# NFCard.net
KiCad netlist of a schematic drawn in Altium Designer
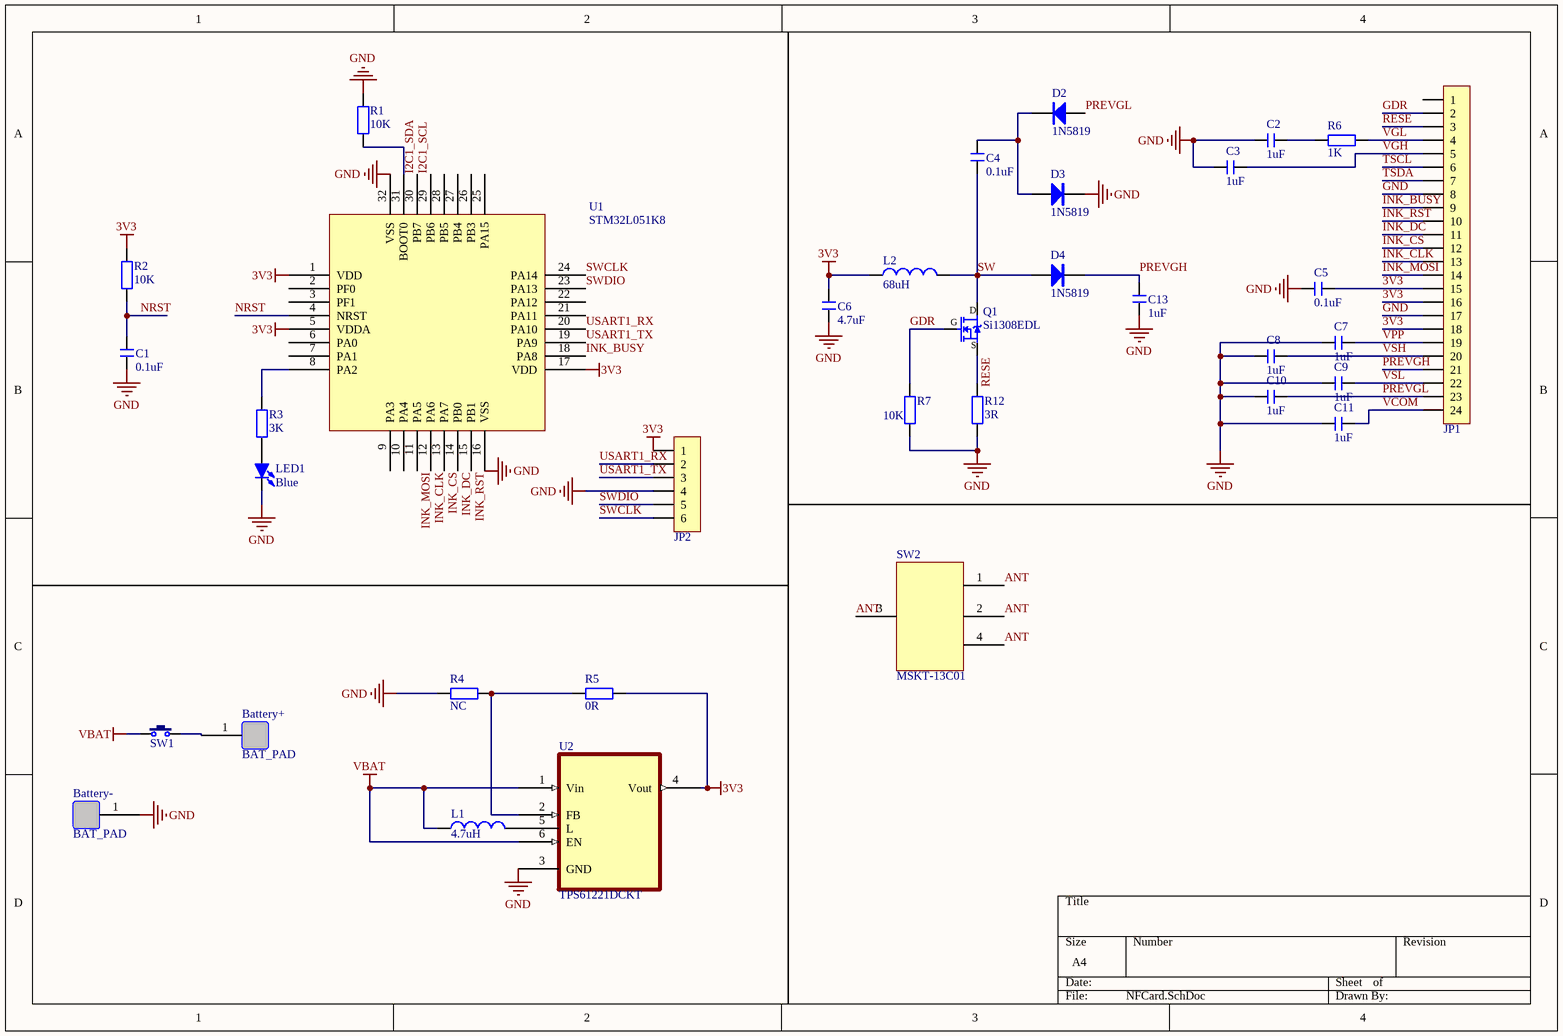
[diagram p0: NFCard.SchDoc]

(export (version "E")
  (design (tool "Eeschema 10.0.6"))
  (components
    (comp (ref "Battery+")
      (value "BAT_PAD")
      (footprint "BAT_PAD")
      (libsource (lib "15.1 - 未分类器件") (part "BAT_PAD"))
    )
    (comp (ref "Battery-")
      (value "BAT_PAD")
      (footprint "BAT_PAD")
      (libsource (lib "15.1 - 未分类器件") (part "BAT_PAD"))
    )
    (comp (ref "C1")
      (value "0.1uF")
      (footprint "C 0603_L")
      (description "无极性贴片电容")
      (fields (field (name "版权归属") "源创客"))
      (libsource (lib "3.1   - 电阻-电容-电感") (part "C"))
    )
    (comp (ref "C2")
      (value "1uF")
      (footprint "C 0603_L")
      (description "无极性贴片电容")
      (fields (field (name "版权归属") "源创客"))
      (libsource (lib "3.1   - 电阻-电容-电感") (part "C"))
    )
    (comp (ref "C3")
      (value "1uF")
      (footprint "C 0603_L")
      (description "无极性贴片电容")
      (fields (field (name "版权归属") "源创客"))
      (libsource (lib "3.1   - 电阻-电容-电感") (part "C"))
    )
    (comp (ref "C4")
      (value "0.1uF")
      (footprint "C 0603_L")
      (description "无极性贴片电容")
      (fields (field (name "版权归属") "源创客"))
      (libsource (lib "3.1   - 电阻-电容-电感") (part "C"))
    )
    (comp (ref "C5")
      (value "0.1uF")
      (footprint "C 0603_L")
      (description "无极性贴片电容")
      (fields (field (name "版权归属") "源创客"))
      (libsource (lib "3.1   - 电阻-电容-电感") (part "C"))
    )
    (comp (ref "C6")
      (value "4.7uF")
      (footprint "C 0603_L")
      (description "无极性贴片电容")
      (fields (field (name "版权归属") "源创客"))
      (libsource (lib "3.1   - 电阻-电容-电感") (part "C"))
    )
    (comp (ref "C7")
      (value "1uF")
      (footprint "C 0603_L")
      (description "无极性贴片电容")
      (fields (field (name "版权归属") "源创客"))
      (libsource (lib "3.1   - 电阻-电容-电感") (part "C"))
    )
    (comp (ref "C8")
      (value "1uF")
      (footprint "C 0603_L")
      (description "无极性贴片电容")
      (fields (field (name "版权归属") "源创客"))
      (libsource (lib "3.1   - 电阻-电容-电感") (part "C"))
    )
    (comp (ref "C9")
      (value "1uF")
      (footprint "C 0603_L")
      (description "无极性贴片电容")
      (fields (field (name "版权归属") "源创客"))
      (libsource (lib "3.1   - 电阻-电容-电感") (part "C"))
    )
    (comp (ref "C10")
      (value "1uF")
      (footprint "C 0603_L")
      (description "无极性贴片电容")
      (fields (field (name "版权归属") "源创客"))
      (libsource (lib "3.1   - 电阻-电容-电感") (part "C"))
    )
    (comp (ref "C11")
      (value "1uF")
      (footprint "C 0603_L")
      (description "无极性贴片电容")
      (fields (field (name "版权归属") "源创客"))
      (libsource (lib "3.1   - 电阻-电容-电感") (part "C"))
    )
    (comp (ref "C13")
      (value "1uF")
      (footprint "C 0603_L")
      (description "无极性贴片电容")
      (fields (field (name "版权归属") "源创客"))
      (libsource (lib "3.1   - 电阻-电容-电感") (part "C"))
    )
    (comp (ref "D2")
      (value "1N5819")
      (footprint "SOD-323")
      (description "肖特基二极管")
      (fields (field (name "版权归属") "源创客"))
      (libsource (lib "8.1   - 二极管-整流桥") (part "1N5819"))
    )
    (comp (ref "D3")
      (value "1N5819")
      (footprint "SOD-323")
      (description "肖特基二极管")
      (fields (field (name "版权归属") "源创客"))
      (libsource (lib "8.1   - 二极管-整流桥") (part "1N5819"))
    )
    (comp (ref "D4")
      (value "1N5819")
      (footprint "SOD-323")
      (description "肖特基二极管")
      (fields (field (name "版权归属") "源创客"))
      (libsource (lib "8.1   - 二极管-整流桥") (part "1N5819"))
    )
    (comp (ref "JP1")
      (value "FPC1.0-24P")
      (footprint "FPC0.5 CB-24P")
      (description "FPC连接器")
      (fields (field (name "版权归属") "源创客"))
      (libsource (lib "4.15 - FPC连接器") (part "FPC-24P"))
    )
    (comp (ref "JP2")
      (value "HDR-1X6")
      (footprint "HDR1.27-M-6P-S")
      (description "6P接插件")
      (fields (field (name "版权归属") "源创客"))
      (libsource (lib "4.3   - 接插件-脚距1.27") (part "Header 6"))
    )
    (comp (ref "L1")
      (value "4.7uH")
      (footprint "L 0805_L")
      (description "小功率贴片电感")
      (fields (field (name "版权归属") "源创客"))
      (libsource (lib "3.1   - 电阻-电容-电感") (part "L"))
    )
    (comp (ref "L2")
      (value "68uH")
      (footprint "FB 2520_L")
      (description "小功率贴片电感")
      (fields (field (name "版权归属") "源创客"))
      (libsource (lib "3.1   - 电阻-电容-电感") (part "L"))
    )
    (comp (ref "LED1")
      (value "Blue")
      (footprint "LED 0603B")
      (description "贴片LED")
      (fields (field (name "版权归属") "源创客"))
      (libsource (lib "9.1   - LED") (part "LED-SMD"))
    )
    (comp (ref "Q1")
      (value "Si1308EDL")
      (footprint "SOT23-3L")
      (description "N沟道 30V/4.2A")
      (fields (field (name "版权归属") "源创客"))
      (libsource (lib "6.1   - 场效应管-可控硅") (part "AO3400"))
    )
    (comp (ref "R1")
      (value "10K")
      (footprint "R 0603_L")
      (description "贴片电阻")
      (fields (field (name "版权归属") "源创客"))
      (libsource (lib "3.1   - 电阻-电容-电感") (part "R"))
    )
    (comp (ref "R2")
      (value "10K")
      (footprint "R 0603_L")
      (description "贴片电阻")
      (fields (field (name "版权归属") "源创客"))
      (libsource (lib "3.1   - 电阻-电容-电感") (part "R"))
    )
    (comp (ref "R3")
      (value "3K")
      (footprint "R 0603_L")
      (description "贴片电阻")
      (fields (field (name "版权归属") "源创客"))
      (libsource (lib "3.1   - 电阻-电容-电感") (part "R"))
    )
    (comp (ref "R4")
      (value "NC")
      (footprint "R 0603_L")
      (description "贴片电阻")
      (fields (field (name "版权归属") "源创客"))
      (libsource (lib "3.1   - 电阻-电容-电感") (part "R"))
    )
    (comp (ref "R5")
      (value "0R")
      (footprint "R 0603_L")
      (description "贴片电阻")
      (fields (field (name "版权归属") "源创客"))
      (libsource (lib "3.1   - 电阻-电容-电感") (part "R"))
    )
    (comp (ref "R6")
      (value "1K")
      (footprint "R 0603_L")
      (description "贴片电阻")
      (fields (field (name "版权归属") "源创客"))
      (libsource (lib "3.1   - 电阻-电容-电感") (part "R"))
    )
    (comp (ref "R7")
      (value "10K")
      (footprint "R 0603_L")
      (description "贴片电阻")
      (fields (field (name "版权归属") "源创客"))
      (libsource (lib "3.1   - 电阻-电容-电感") (part "R"))
    )
    (comp (ref "R12")
      (value "3R")
      (footprint "R 0603_L")
      (description "贴片电阻")
      (fields (field (name "版权归属") "源创客"))
      (libsource (lib "3.1   - 电阻-电容-电感") (part "R"))
    )
    (comp (ref "SW1")
      (value "3x6x5")
      (footprint "TSW SMD-3*4*2")
      (description "3x6轻触开关")
      (fields (field (name "版权归属") "源创客"))
      (libsource (lib "5.1   - 按键-开关") (part "TSW 3x6"))
    )
    (comp (ref "SW2")
      (value "MSKT-13C01")
      (footprint "MSKT-13C01")
      (description "七脚拨动开关")
      (libsource (lib "5.1   - 按键-开关") (part "MSKT-13C01"))
    )
    (comp (ref "U1")
      (value "STM32L051K8")
      (footprint "TQFP32 7x7_N")
      (libsource (lib "2.1   - STM32系列单片机") (part "STM32L051K8"))
    )
    (comp (ref "U2")
      (value "TPS61221DCKT")
      (footprint "SOT23-6L")
      (libsource (lib "1.3   - 电源类芯片") (part "TPS61221DCKT"))
    )
  )
  (nets
    (net (code "1") (name "/ANT") (class "Default")
      (node (ref "SW2") (pin "1") (pintype "passive"))
      (node (ref "SW2") (pin "2") (pintype "passive"))
      (node (ref "SW2") (pin "3") (pintype "passive"))
      (node (ref "SW2") (pin "4") (pintype "passive"))
    )
    (net (code "2") (name "/GDR") (class "Default")
      (node (ref "JP1") (pin "2") (pinfunction "2_2") (pintype "passive"))
      (node (ref "Q1") (pin "1") (pinfunction "G_1") (pintype "passive"))
      (node (ref "R7") (pin "2") (pinfunction "2_2") (pintype "passive"))
    )
    (net (code "3") (name "/I2C1_SCL") (class "Default")
      (node (ref "U1") (pin "29") (pinfunction "PB6_29") (pintype "passive"))
    )
    (net (code "4") (name "/I2C1_SDA") (class "Default")
      (node (ref "U1") (pin "30") (pinfunction "PB7_30") (pintype "passive"))
    )
    (net (code "5") (name "/INK_BUSY") (class "Default")
      (node (ref "JP1") (pin "9") (pinfunction "9_9") (pintype "passive"))
      (node (ref "U1") (pin "18") (pinfunction "PA8_18") (pintype "passive"))
    )
    (net (code "6") (name "/INK_CLK") (class "Default")
      (node (ref "JP1") (pin "13") (pinfunction "13_13") (pintype "passive"))
      (node (ref "U1") (pin "12") (pinfunction "PA6_12") (pintype "passive"))
    )
    (net (code "7") (name "/INK_CS") (class "Default")
      (node (ref "JP1") (pin "12") (pinfunction "12_12") (pintype "passive"))
      (node (ref "U1") (pin "13") (pinfunction "PA7_13") (pintype "passive"))
    )
    (net (code "8") (name "/INK_DC") (class "Default")
      (node (ref "JP1") (pin "11") (pinfunction "11_11") (pintype "passive"))
      (node (ref "U1") (pin "14") (pinfunction "PB0_14") (pintype "passive"))
    )
    (net (code "9") (name "/INK_MOSI") (class "Default")
      (node (ref "JP1") (pin "14") (pinfunction "14_14") (pintype "passive"))
      (node (ref "U1") (pin "11") (pinfunction "PA5_11") (pintype "passive"))
    )
    (net (code "10") (name "/INK_RST") (class "Default")
      (node (ref "JP1") (pin "10") (pinfunction "10_10") (pintype "passive"))
      (node (ref "U1") (pin "15") (pinfunction "PB1_15") (pintype "passive"))
    )
    (net (code "11") (name "/NRST") (class "Default")
      (node (ref "C1") (pin "2") (pinfunction "2_2") (pintype "passive"))
      (node (ref "R2") (pin "1") (pinfunction "1_1") (pintype "passive"))
      (node (ref "U1") (pin "4") (pinfunction "NRST_4") (pintype "passive"))
    )
    (net (code "12") (name "/PREVGH") (class "Default")
      (node (ref "C13") (pin "2") (pinfunction "2_2") (pintype "passive"))
      (node (ref "D4") (pin "2") (pinfunction "K_2") (pintype "passive"))
      (node (ref "JP1") (pin "21") (pinfunction "21_21") (pintype "passive"))
    )
    (net (code "13") (name "/PREVGL") (class "Default")
      (node (ref "C10") (pin "2") (pinfunction "2_2") (pintype "passive"))
      (node (ref "D2") (pin "1") (pinfunction "A_1") (pintype "passive"))
      (node (ref "JP1") (pin "23") (pinfunction "23_23") (pintype "passive"))
    )
    (net (code "14") (name "/RESE") (class "Default")
      (node (ref "JP1") (pin "3") (pinfunction "3_3") (pintype "passive"))
      (node (ref "Q1") (pin "2") (pinfunction "S_2") (pintype "passive"))
      (node (ref "R12") (pin "2") (pinfunction "2_2") (pintype "passive"))
    )
    (net (code "15") (name "/SW") (class "Default")
      (node (ref "C4") (pin "1") (pinfunction "1_1") (pintype "passive"))
      (node (ref "D4") (pin "1") (pinfunction "A_1") (pintype "passive"))
      (node (ref "L2") (pin "2") (pinfunction "2_2") (pintype "passive"))
      (node (ref "Q1") (pin "3") (pinfunction "D_3") (pintype "passive"))
    )
    (net (code "16") (name "/SWCLK") (class "Default")
      (node (ref "JP2") (pin "6") (pinfunction "6_6") (pintype "passive"))
      (node (ref "U1") (pin "24") (pinfunction "PA14_24") (pintype "passive"))
    )
    (net (code "17") (name "/SWDIO") (class "Default")
      (node (ref "JP2") (pin "5") (pinfunction "5_5") (pintype "passive"))
      (node (ref "U1") (pin "23") (pinfunction "PA13_23") (pintype "passive"))
    )
    (net (code "18") (name "/TSCL") (class "Default")
      (node (ref "JP1") (pin "6") (pinfunction "6_6") (pintype "passive"))
    )
    (net (code "19") (name "/TSDA") (class "Default")
      (node (ref "JP1") (pin "7") (pinfunction "7_7") (pintype "passive"))
    )
    (net (code "20") (name "/USART1_RX") (class "Default")
      (node (ref "JP2") (pin "2") (pinfunction "2_2") (pintype "passive"))
      (node (ref "U1") (pin "20") (pinfunction "PA10_20") (pintype "passive"))
    )
    (net (code "21") (name "/USART1_TX") (class "Default")
      (node (ref "JP2") (pin "3") (pinfunction "3_3") (pintype "passive"))
      (node (ref "U1") (pin "19") (pinfunction "PA9_19") (pintype "passive"))
    )
    (net (code "22") (name "/VCOM") (class "Default")
      (node (ref "C11") (pin "2") (pinfunction "2_2") (pintype "passive"))
      (node (ref "JP1") (pin "24") (pinfunction "24_24") (pintype "passive"))
    )
    (net (code "23") (name "/VGH") (class "Default")
      (node (ref "C3") (pin "2") (pinfunction "2_2") (pintype "passive"))
      (node (ref "JP1") (pin "5") (pinfunction "5_5") (pintype "passive"))
    )
    (net (code "24") (name "/VGL") (class "Default")
      (node (ref "JP1") (pin "4") (pinfunction "4_4") (pintype "passive"))
      (node (ref "R6") (pin "2") (pinfunction "2_2") (pintype "passive"))
    )
    (net (code "25") (name "/VPP") (class "Default")
      (node (ref "C7") (pin "2") (pinfunction "2_2") (pintype "passive"))
      (node (ref "JP1") (pin "19") (pinfunction "19_19") (pintype "passive"))
    )
    (net (code "26") (name "/VSH") (class "Default")
      (node (ref "C8") (pin "2") (pinfunction "2_2") (pintype "passive"))
      (node (ref "JP1") (pin "20") (pinfunction "20_20") (pintype "passive"))
    )
    (net (code "27") (name "/VSL") (class "Default")
      (node (ref "C9") (pin "2") (pinfunction "2_2") (pintype "passive"))
      (node (ref "JP1") (pin "22") (pinfunction "22_22") (pintype "passive"))
    )
    (net (code "28") (name "3V3") (class "Default")
      (node (ref "C5") (pin "2") (pinfunction "2_2") (pintype "passive"))
      (node (ref "C6") (pin "2") (pinfunction "2_2") (pintype "passive"))
      (node (ref "JP1") (pin "15") (pinfunction "15_15") (pintype "passive"))
      (node (ref "JP1") (pin "16") (pinfunction "16_16") (pintype "passive"))
      (node (ref "JP1") (pin "18") (pinfunction "18_18") (pintype "passive"))
      (node (ref "JP2") (pin "1") (pinfunction "1_1") (pintype "passive"))
      (node (ref "L2") (pin "1") (pinfunction "1_1") (pintype "passive"))
      (node (ref "R2") (pin "2") (pinfunction "2_2") (pintype "passive"))
      (node (ref "R5") (pin "2") (pinfunction "2_2") (pintype "passive"))
      (node (ref "U1") (pin "1") (pinfunction "VDD_1") (pintype "passive"))
      (node (ref "U1") (pin "17") (pinfunction "VDD_17") (pintype "passive"))
      (node (ref "U1") (pin "5") (pinfunction "VDDA_5") (pintype "passive"))
      (node (ref "U2") (pin "4") (pinfunction "Vout_4") (pintype "output"))
    )
    (net (code "29") (name "GND") (class "Default")
      (node (ref "Battery-") (pin "1") (pintype "passive"))
      (node (ref "C1") (pin "1") (pinfunction "1_1") (pintype "passive"))
      (node (ref "C10") (pin "1") (pinfunction "1_1") (pintype "passive"))
      (node (ref "C11") (pin "1") (pinfunction "1_1") (pintype "passive"))
      (node (ref "C13") (pin "1") (pinfunction "1_1") (pintype "passive"))
      (node (ref "C2") (pin "1") (pinfunction "1_1") (pintype "passive"))
      (node (ref "C3") (pin "1") (pinfunction "1_1") (pintype "passive"))
      (node (ref "C5") (pin "1") (pinfunction "1_1") (pintype "passive"))
      (node (ref "C6") (pin "1") (pinfunction "1_1") (pintype "passive"))
      (node (ref "C7") (pin "1") (pinfunction "1_1") (pintype "passive"))
      (node (ref "C8") (pin "1") (pinfunction "1_1") (pintype "passive"))
      (node (ref "C9") (pin "1") (pinfunction "1_1") (pintype "passive"))
      (node (ref "D3") (pin "2") (pinfunction "K_2") (pintype "passive"))
      (node (ref "JP1") (pin "17") (pinfunction "17_17") (pintype "passive"))
      (node (ref "JP1") (pin "8") (pinfunction "8_8") (pintype "passive"))
      (node (ref "JP2") (pin "4") (pinfunction "4_4") (pintype "passive"))
      (node (ref "LED1") (pin "2") (pinfunction "K_2") (pintype "passive"))
      (node (ref "R1") (pin "2") (pinfunction "2_2") (pintype "passive"))
      (node (ref "R12") (pin "1") (pinfunction "1_1") (pintype "passive"))
      (node (ref "R4") (pin "1") (pinfunction "1_1") (pintype "passive"))
      (node (ref "R7") (pin "1") (pinfunction "1_1") (pintype "passive"))
      (node (ref "U1") (pin "16") (pinfunction "VSS_16") (pintype "passive"))
      (node (ref "U1") (pin "32") (pinfunction "VSS_32") (pintype "passive"))
      (node (ref "U2") (pin "3") (pinfunction "GND_3") (pintype "passive"))
    )
    (net (code "30") (name "Net-(Battery+-Pad1)") (class "Default")
      (node (ref "Battery+") (pin "1") (pintype "passive"))
      (node (ref "SW1") (pin "2") (pinfunction "2_2") (pintype "passive"))
    )
    (net (code "31") (name "Net-(C2-Pad2)") (class "Default")
      (node (ref "C2") (pin "2") (pinfunction "2_2") (pintype "passive"))
      (node (ref "R6") (pin "1") (pinfunction "1_1") (pintype "passive"))
    )
    (net (code "32") (name "Net-(D2-K)") (class "Default")
      (node (ref "C4") (pin "2") (pinfunction "2_2") (pintype "passive"))
      (node (ref "D2") (pin "2") (pinfunction "K_2") (pintype "passive"))
      (node (ref "D3") (pin "1") (pinfunction "A_1") (pintype "passive"))
    )
    (net (code "33") (name "Net-(LED1-A)") (class "Default")
      (node (ref "LED1") (pin "1") (pinfunction "A_1") (pintype "passive"))
      (node (ref "R3") (pin "1") (pinfunction "1_1") (pintype "passive"))
    )
    (net (code "34") (name "Net-(U1-BOOT0)") (class "Default")
      (node (ref "R1") (pin "1") (pinfunction "1_1") (pintype "passive"))
      (node (ref "U1") (pin "31") (pinfunction "BOOT0_31") (pintype "passive"))
    )
    (net (code "35") (name "Net-(U1-PA2)") (class "Default")
      (node (ref "R3") (pin "2") (pinfunction "2_2") (pintype "passive"))
      (node (ref "U1") (pin "8") (pinfunction "PA2_8") (pintype "passive"))
    )
    (net (code "36") (name "Net-(U2-FB)") (class "Default")
      (node (ref "R4") (pin "2") (pinfunction "2_2") (pintype "passive"))
      (node (ref "R5") (pin "1") (pinfunction "1_1") (pintype "passive"))
      (node (ref "U2") (pin "2") (pinfunction "FB_2") (pintype "input"))
    )
    (net (code "37") (name "Net-(U2-L)") (class "Default")
      (node (ref "L1") (pin "2") (pinfunction "2_2") (pintype "passive"))
      (node (ref "U2") (pin "5") (pinfunction "L_5") (pintype "passive"))
    )
    (net (code "38") (name "VBAT") (class "Default")
      (node (ref "L1") (pin "1") (pinfunction "1_1") (pintype "passive"))
      (node (ref "SW1") (pin "1") (pinfunction "1_1") (pintype "passive"))
      (node (ref "U2") (pin "1") (pinfunction "Vin_1") (pintype "input"))
      (node (ref "U2") (pin "6") (pinfunction "EN_6") (pintype "input"))
    )
    (net (code "39") (name "unconnected-(JP1-Pad1)") (class "Default")
      (node (ref "JP1") (pin "1") (pinfunction "1_1") (pintype "passive"))
    )
    (net (code "40") (name "unconnected-(U1-PA0-Pad6)") (class "Default")
      (node (ref "U1") (pin "6") (pinfunction "PA0_6") (pintype "passive"))
    )
    (net (code "41") (name "unconnected-(U1-PA1-Pad7)") (class "Default")
      (node (ref "U1") (pin "7") (pinfunction "PA1_7") (pintype "passive"))
    )
    (net (code "42") (name "unconnected-(U1-PA3-Pad9)") (class "Default")
      (node (ref "U1") (pin "9") (pinfunction "PA3_9") (pintype "passive"))
    )
    (net (code "43") (name "unconnected-(U1-PA4-Pad10)") (class "Default")
      (node (ref "U1") (pin "10") (pinfunction "PA4_10") (pintype "passive"))
    )
    (net (code "44") (name "unconnected-(U1-PA11-Pad21)") (class "Default")
      (node (ref "U1") (pin "21") (pinfunction "PA11_21") (pintype "passive"))
    )
    (net (code "45") (name "unconnected-(U1-PA12-Pad22)") (class "Default")
      (node (ref "U1") (pin "22") (pinfunction "PA12_22") (pintype "passive"))
    )
    (net (code "46") (name "unconnected-(U1-PA15-Pad25)") (class "Default")
      (node (ref "U1") (pin "25") (pinfunction "PA15_25") (pintype "passive"))
    )
    (net (code "47") (name "unconnected-(U1-PB3-Pad26)") (class "Default")
      (node (ref "U1") (pin "26") (pinfunction "PB3_26") (pintype "passive"))
    )
    (net (code "48") (name "unconnected-(U1-PB4-Pad27)") (class "Default")
      (node (ref "U1") (pin "27") (pinfunction "PB4_27") (pintype "passive"))
    )
    (net (code "49") (name "unconnected-(U1-PB5-Pad28)") (class "Default")
      (node (ref "U1") (pin "28") (pinfunction "PB5_28") (pintype "passive"))
    )
    (net (code "50") (name "unconnected-(U1-PF0-Pad2)") (class "Default")
      (node (ref "U1") (pin "2") (pinfunction "PF0_2") (pintype "passive"))
    )
    (net (code "51") (name "unconnected-(U1-PF1-Pad3)") (class "Default")
      (node (ref "U1") (pin "3") (pinfunction "PF1_3") (pintype "passive"))
    )
  )
)
